# hv-indicator.net
KiCad netlist of a schematic drawn in Altium Designer
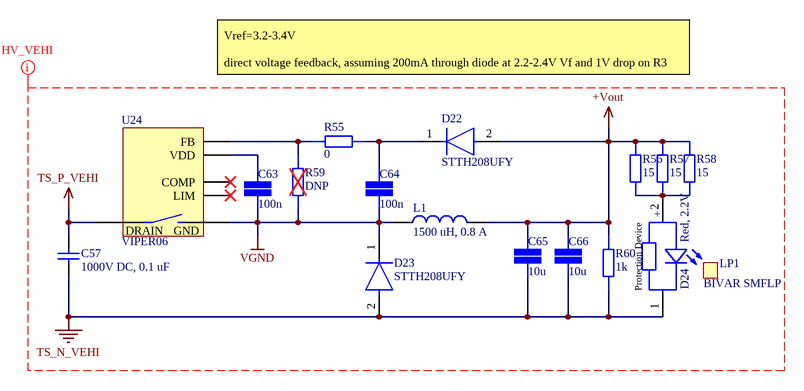
[diagram p0: hv-indicator.SchDoc]

(export (version "E")
  (design (tool "Eeschema 10.0.6"))
  (components
    (comp (ref "C57")
      (value "1000V DC, 0.1 uF")
      (footprint "WCAP-FTBE_18x8.5x15")
      (description "WCAP-FTBE Film Capacitors, 18x8.5x15mm, 1000V DC, 0.1 uF")
      (fields (field (name "PART NUMBER") "890493425009CS") (field (name "PUBLISHER") "Wurth Elektronik"))
      (libsource (lib "ALTIUM-WCAP-FTBE-rev17a") (part "890493425009CS"))
    )
    (comp (ref "C63")
      (value "100n")
      (footprint "CAP 0603/1608")
      (description "Capacitor with multiple Footprints")
      (fields (field (name "VOLTAGE") "6.3V") (field (name "Comment") "SMD Capacitor"))
      (libsource (lib "Standardbauteile") (part "SMD Capacitor"))
    )
    (comp (ref "C64")
      (value "100n")
      (footprint "CAP 0603/1608")
      (description "Capacitor with multiple Footprints")
      (fields (field (name "VOLTAGE") "6.3V") (field (name "Comment") "SMD Capacitor"))
      (libsource (lib "Standardbauteile") (part "SMD Capacitor"))
    )
    (comp (ref "C65")
      (value "10u")
      (footprint "CAP 1206/3216")
      (description "Capacitor with multiple Footprints")
      (fields (field (name "VOLTAGE") "6.3V") (field (name "Comment") "SMD Capacitor"))
      (libsource (lib "Standardbauteile") (part "SMD Capacitor"))
    )
    (comp (ref "C66")
      (value "10u")
      (footprint "CAP 1206/3216")
      (description "Capacitor with multiple Footprints")
      (fields (field (name "VOLTAGE") "6.3V") (field (name "Comment") "SMD Capacitor"))
      (libsource (lib "Standardbauteile") (part "SMD Capacitor"))
    )
    (comp (ref "D22")
      (value "STTH208UFY")
      (footprint "FP-SMBflat-MFG")
      (description "DIODE GEN PURP 800V 2A SMBFLAT")
      (libsource (lib "Altium Content Vault") (part "bbad89a4e1b75021f221062c6e04887"))
    )
    (comp (ref "D23")
      (value "STTH208UFY")
      (footprint "FP-SMBflat-MFG")
      (description "DIODE GEN PURP 800V 2A SMBFLAT")
      (libsource (lib "Altium Content Vault") (part "bbad89a4e1b75021f221062c6e04887"))
    )
    (comp (ref "D24")
      (value "Red, 2.2V")
      (footprint "WL-SMDC_3535")
      (description "WL-SMDC SMT Mono-color Ceramic LED Waterclear, size 3535, 2.2V, Red")
      (fields
        (field (name "MANUFACTURER PART NUMBER") "150353RS74500")
        (field (name "MANUFACTURER") "Wurth Elektronik")
      )
      (libsource (lib "Altium_WL-SMDC (rev20a)") (part "150353RS74500"))
    )
    (comp (ref "L1")
      (value "1500 uH, 0.8 A")
      (footprint "WE-PD_1210_Metal base")
      (description "WE-PD SMT Shielded Power Inductor, size 1210, 1500 uH, 0.8 A")
      (fields (field (name "PART NUMBER") "7447709152") (field (name "PUBLISHER") "Wurth Elektronik"))
      (libsource (lib "ALTIUM-WE-PD-rev18b") (part "7447709152"))
    )
    (comp (ref "LP1")
      (value "BIVAR SMFLP")
      (footprint "BIVAR_SMFLP")
      (libsource (lib "Standardbauteile") (part "BIVAR_SMFLP"))
    )
    (comp (ref "R55")
      (value "0")
      (footprint "STACKPOLE CSR0603")
      (description "Resistor with multiple footprints")
      (fields (field (name "Comment") "SMD Resistor"))
      (libsource (lib "Standardbauteile") (part "SMD Resistor"))
    )
    (comp (ref "R56")
      (value "15")
      (footprint "STACKPOLE CSR1206")
      (description "Resistor with multiple footprints")
      (fields (field (name "Comment") "SMD Resistor"))
      (libsource (lib "Standardbauteile") (part "SMD Resistor"))
    )
    (comp (ref "R57")
      (value "15")
      (footprint "STACKPOLE CSR1206")
      (description "Resistor with multiple footprints")
      (fields (field (name "Comment") "SMD Resistor"))
      (libsource (lib "Standardbauteile") (part "SMD Resistor"))
    )
    (comp (ref "R58")
      (value "15")
      (footprint "STACKPOLE CSR1206")
      (description "Resistor with multiple footprints")
      (fields (field (name "Comment") "SMD Resistor"))
      (libsource (lib "Standardbauteile") (part "SMD Resistor"))
    )
    (comp (ref "R59")
      (value "DNP")
      (footprint "STACKPOLE CSR0603")
      (description "Resistor with multiple footprints")
      (fields (field (name "Comment") "SMD Resistor"))
      (libsource (lib "Standardbauteile") (part "SMD Resistor"))
    )
    (comp (ref "R60")
      (value "1k")
      (footprint "STACKPOLE CSR0603")
      (description "Resistor with multiple footprints")
      (fields (field (name "Comment") "SMD Resistor"))
      (libsource (lib "Standardbauteile") (part "SMD Resistor"))
    )
    (comp (ref "U24")
      (value "VIPER06")
      (footprint "SSO10_VIPER06")
      (description "Energy saving high voltage converter for direct feedback")
      (libsource (lib "TSC") (part "VIPER06"))
    )
  )
  (nets
    (net (code "1") (name "+Vout") (class "Default")
      (node (ref "C65") (pin "2") (pinfunction "2_2") (pintype "passive"))
      (node (ref "C66") (pin "2") (pinfunction "2_2") (pintype "passive"))
      (node (ref "D22") (pin "2") (pinfunction "A_2") (pintype "passive"))
      (node (ref "L1") (pin "2") (pinfunction "2_2") (pintype "passive"))
      (node (ref "R56") (pin "1") (pinfunction "1_1") (pintype "passive"))
      (node (ref "R57") (pin "1") (pinfunction "1_1") (pintype "passive"))
      (node (ref "R58") (pin "1") (pinfunction "1_1") (pintype "passive"))
      (node (ref "R60") (pin "2") (pinfunction "2_2") (pintype "passive"))
    )
    (net (code "2") (name "Net-(D22-K)") (class "Default")
      (node (ref "C64") (pin "2") (pinfunction "2_2") (pintype "passive"))
      (node (ref "D22") (pin "1") (pinfunction "K_1") (pintype "passive"))
      (node (ref "R55") (pin "1") (pinfunction "1_1") (pintype "passive"))
    )
    (net (code "3") (name "Net-(D24-A)") (class "Default")
      (node (ref "D24") (pin "2") (pinfunction "A_2") (pintype "passive"))
      (node (ref "R56") (pin "2") (pinfunction "2_2") (pintype "passive"))
      (node (ref "R57") (pin "2") (pinfunction "2_2") (pintype "passive"))
      (node (ref "R58") (pin "2") (pinfunction "2_2") (pintype "passive"))
    )
    (net (code "4") (name "Net-(U24-FB)") (class "Default")
      (node (ref "R55") (pin "2") (pinfunction "2_2") (pintype "passive"))
      (node (ref "R59") (pin "2") (pinfunction "2_2") (pintype "passive"))
      (node (ref "U24") (pin "4") (pinfunction "FB_4") (pintype "passive"))
    )
    (net (code "5") (name "Net-(U24-VDD)") (class "Default")
      (node (ref "C63") (pin "2") (pinfunction "2_2") (pintype "passive"))
      (node (ref "U24") (pin "2") (pinfunction "VDD_2") (pintype "passive"))
    )
    (net (code "6") (name "TS_N_VEHI") (class "Default")
      (node (ref "C57") (pin "1") (pinfunction "1_1") (pintype "passive"))
      (node (ref "C65") (pin "1") (pinfunction "1_1") (pintype "passive"))
      (node (ref "C66") (pin "1") (pinfunction "1_1") (pintype "passive"))
      (node (ref "D23") (pin "2") (pinfunction "A_2") (pintype "passive"))
      (node (ref "D24") (pin "1") (pinfunction "K_1") (pintype "passive"))
      (node (ref "R60") (pin "1") (pinfunction "1_1") (pintype "passive"))
    )
    (net (code "7") (name "TS_P_VEHI") (class "Default")
      (node (ref "C57") (pin "2") (pinfunction "2_2") (pintype "passive"))
      (node (ref "U24") (pin "6") (pinfunction "DRAIN_6") (pintype "passive"))
    )
    (net (code "8") (name "VGND") (class "Default")
      (node (ref "C63") (pin "1") (pinfunction "1_1") (pintype "passive"))
      (node (ref "C64") (pin "1") (pinfunction "1_1") (pintype "passive"))
      (node (ref "D23") (pin "1") (pinfunction "K_1") (pintype "passive"))
      (node (ref "L1") (pin "1") (pinfunction "1_1") (pintype "passive"))
      (node (ref "R59") (pin "1") (pinfunction "1_1") (pintype "passive"))
      (node (ref "U24") (pin "1") (pinfunction "GND_1") (pintype "passive"))
    )
    (net (code "9") (name "unconnected-(U24-COMP-Pad5)") (class "Default")
      (node (ref "U24") (pin "5") (pinfunction "COMP_5") (pintype "passive+no_connect"))
    )
    (net (code "10") (name "unconnected-(U24-LIM-Pad3)") (class "Default")
      (node (ref "U24") (pin "3") (pinfunction "LIM_3") (pintype "passive+no_connect"))
    )
  )
)
